# Arduino_extension_connectors.net
KiCad netlist of a schematic drawn in Altium Designer
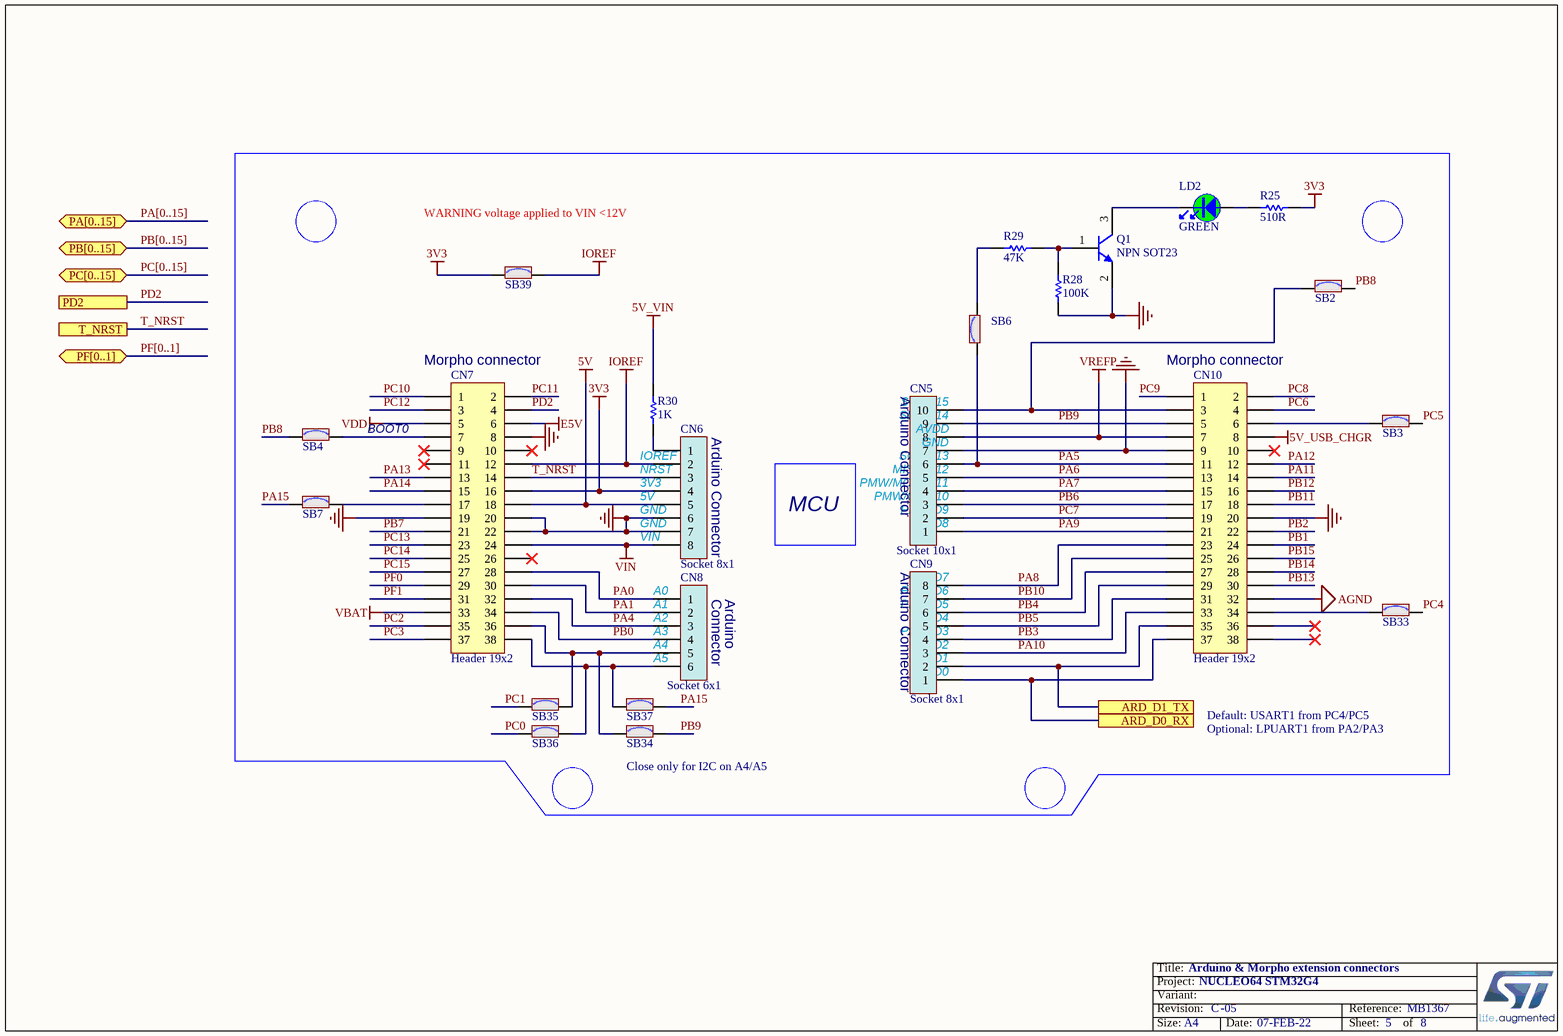
[diagram p0: Arduino_extension_connectors.SchDoc]

(export (version "E")
  (design (tool "Eeschema 10.0.6"))
  (components
    (comp (ref "CN5")
      (value "Socket 10x1")
      (footprint "CON_SAMTEC_SSW-110-03-X-S")
      (description "Socket, 10x1, 2.54mm, VR, TH, Height 8.51mm/10mm")
      (fields
        (field (name "INTERNAL_PART_NUMBER") "MCD-00262")
        (field (name "MANUFACTURER_PART_NUMBER") "SSW-110-03-x-S")
        (field (name "PROVIDED_BY") "SUBCO")
      )
      (libsource (lib "MCD_PARTS_database") (part "Socket 10x1"))
    )
    (comp (ref "CN6")
      (value "Socket 8x1")
      (footprint "CON_SAMTEC_SSW-108-03-X-S")
      (description "Socket, 8x1, 2.54mm, VR, TH, Height 8.51mm/10mm")
      (fields
        (field (name "INTERNAL_PART_NUMBER") "MCD-00261")
        (field (name "MANUFACTURER_PART_NUMBER") "SSW-108-03-x-S")
        (field (name "PROVIDED_BY") "SUBCO")
      )
      (libsource (lib "MCD_PARTS_database") (part "Socket 8x1"))
    )
    (comp (ref "CN7")
      (value "Header 19x2")
      (footprint "CON_SAMTEC_TSW-119-09-X-D")
      (description "Header, 19x2, 2,54mm, VR, TH, Height 5.84mm/10.16mm")
      (fields
        (field (name "INTERNAL_PART_NUMBER") "MCD-00213")
        (field (name "MANUFACTURER_PART_NUMBER") "TSW-119-09-x-D")
        (field (name "PROVIDED_BY") "SUBCO")
      )
      (libsource (lib "MCD_PARTS_database") (part "Header 19x2"))
    )
    (comp (ref "CN8")
      (value "Socket 6x1")
      (footprint "CON_SAMTEC_SSW-106-03-X-S")
      (description "Socket, 6x1, 2.54mm, VR, TH, Height 8.51mm/10mm")
      (fields
        (field (name "INTERNAL_PART_NUMBER") "MCD-00260")
        (field (name "MANUFACTURER_PART_NUMBER") "SSW-106-03-x-S")
        (field (name "PROVIDED_BY") "SUBCO")
      )
      (libsource (lib "MCD_PARTS_database") (part "Socket 6x1"))
    )
    (comp (ref "CN9")
      (value "Socket 8x1")
      (footprint "CON_SAMTEC_SSW-108-03-X-S")
      (description "Socket, 8x1, 2.54mm, VR, TH, Height 8.51mm/10mm")
      (fields
        (field (name "INTERNAL_PART_NUMBER") "MCD-00261")
        (field (name "MANUFACTURER_PART_NUMBER") "SSW-108-03-x-S")
        (field (name "PROVIDED_BY") "SUBCO")
      )
      (libsource (lib "") (part "Socket 8x1_1"))
    )
    (comp (ref "CN10")
      (value "Header 19x2")
      (footprint "CON_SAMTEC_TSW-119-09-X-D")
      (description "Header, 19x2, 2,54mm, VR, TH, Height 5.84mm/10.16mm")
      (fields
        (field (name "INTERNAL_PART_NUMBER") "MCD-00213")
        (field (name "MANUFACTURER_PART_NUMBER") "TSW-119-09-x-D")
        (field (name "PROVIDED_BY") "SUBCO")
      )
      (libsource (lib "MCD_PARTS_database") (part "Header 19x2"))
    )
    (comp (ref "LD2")
      (value "GREEN")
      (footprint "LED_0603_GREEN")
      (description "LED, GREEN, 0603, VF : 2.4V max ; IF: 20mA")
      (fields
        (field (name "INTERNAL_PART_NUMBER") "MCD-02520")
        (field (name "MANUFACTURER") "OSRAM OPTO SEMICONDUCTORS")
      )
      (libsource (lib "MCD_PARTS_database") (part "LED_green"))
    )
    (comp (ref "Q1")
      (value "NPN SOT23")
      (footprint "NPN_SOT23")
      (description "NPN Bipolar Transistor")
      (fields
        (field (name "INTERNAL_PART_NUMBER") "MCD-00073")
        (field (name "MANUFACTURER_PART_NUMBER") "BSR14")
        (field (name "PROVIDED_BY") "SUBCO")
      )
      (libsource (lib "MCD_PARTS_database") (part "9013-SOT23"))
    )
    (comp (ref "R25")
      (value "510R")
      (footprint "R0603")
      (description "Resistor,510R,0603,1%,1/10W")
      (fields
        (field (name "INTERNAL_PART_NUMBER") "MCD-00225")
        (field (name "MANUFACTURER_PART_NUMBER") "RC0603FR-07510RL")
        (field (name "PROVIDED_BY") "SUBCO")
      )
      (libsource (lib "MCD_PARTS_database") (part "Resistor"))
    )
    (comp (ref "R28")
      (value "100K")
      (footprint "R0603")
      (description "Resistor,100K,0603,1%,1/10W")
      (fields
        (field (name "INTERNAL_PART_NUMBER") "MCD-00223")
        (field (name "MANUFACTURER_PART_NUMBER") "RC0603FR-07100KL")
        (field (name "PROVIDED_BY") "Subcon")
      )
      (libsource (lib "MCD_PARTS_database") (part "Resistor"))
    )
    (comp (ref "R29")
      (value "47K")
      (footprint "R0603")
      (description "Resistor,47K,0603,1%,1/10W")
      (fields
        (field (name "INTERNAL_PART_NUMBER") "MCD-00222")
        (field (name "MANUFACTURER_PART_NUMBER") "RC0603FR-0747KL")
        (field (name "PROVIDED_BY") "SUBCO")
      )
      (libsource (lib "MCD_PARTS_database") (part "Resistor"))
    )
    (comp (ref "R30")
      (value "1K")
      (footprint "R0603")
      (description "Resistor,1K,0603,1%,1/10W")
      (fields
        (field (name "INTERNAL_PART_NUMBER") "MCD-00070")
        (field (name "MANUFACTURER_PART_NUMBER") "RC0603FR-071KL")
        (field (name "PROVIDED_BY") "Subcon")
      )
      (libsource (lib "MCD_PARTS_database") (part "Resistor"))
    )
    (comp (ref "SB2")
      (value "~")
      (footprint "SOLDER-BRIDGE_R0603-0R")
      (description "Solder Bridge ON")
      (fields
        (field (name "INTERNAL_PART_NUMBER") "MCD-00071")
        (field (name "MANUFACTURER_PART_NUMBER") "RC0603JR-070RL")
        (field (name "PROVIDED_BY") "SUBCO")
      )
      (libsource (lib "MCD_PARTS_database") (part "SB_ON"))
    )
    (comp (ref "SB3")
      (value "~")
      (footprint "SOLDER-BRIDGE_R0603-0R")
      (description "Solder Bridge ON")
      (fields
        (field (name "INTERNAL_PART_NUMBER") "MCD-00071")
        (field (name "MANUFACTURER_PART_NUMBER") "RC0603JR-070RL")
        (field (name "PROVIDED_BY") "SUBCO")
      )
      (libsource (lib "MCD_PARTS_database") (part "SB_ON"))
    )
    (comp (ref "SB4")
      (value "~")
      (footprint "SOLDER-BRIDGE_R0603-0R")
      (description "Solder Bridge ON")
      (fields
        (field (name "INTERNAL_PART_NUMBER") "MCD-00071")
        (field (name "MANUFACTURER_PART_NUMBER") "RC0603JR-070RL")
        (field (name "PROVIDED_BY") "SUBCO")
      )
      (libsource (lib "MCD_PARTS_database") (part "SB_ON"))
    )
    (comp (ref "SB6")
      (value "~")
      (footprint "SOLDER-BRIDGE_R0603-0R")
      (description "Solder Bridge ON")
      (fields
        (field (name "INTERNAL_PART_NUMBER") "MCD-00071")
        (field (name "MANUFACTURER_PART_NUMBER") "RC0603JR-070RL")
        (field (name "PROVIDED_BY") "SUBCO")
      )
      (libsource (lib "") (part "SB_ON_1"))
    )
    (comp (ref "SB7")
      (value "~")
      (footprint "SOLDER-BRIDGE_R0603-0R")
      (description "Solder Bridge ON")
      (fields
        (field (name "INTERNAL_PART_NUMBER") "MCD-00071")
        (field (name "MANUFACTURER_PART_NUMBER") "RC0603JR-070RL")
        (field (name "PROVIDED_BY") "SUBCO")
      )
      (libsource (lib "MCD_PARTS_database") (part "SB_ON"))
    )
    (comp (ref "SB33")
      (value "~")
      (footprint "SOLDER-BRIDGE_R0603-0R")
      (description "Solder Bridge ON")
      (fields
        (field (name "INTERNAL_PART_NUMBER") "MCD-00071")
        (field (name "MANUFACTURER_PART_NUMBER") "RC0603JR-070RL")
        (field (name "PROVIDED_BY") "SUBCO")
      )
      (libsource (lib "MCD_PARTS_database") (part "SB_ON"))
    )
    (comp (ref "SB34")
      (value "~")
      (footprint "SOLDER-BRIDGE_R0603-0R")
      (description "Solder Bridge ON")
      (fields
        (field (name "INTERNAL_PART_NUMBER") "MCD-00071")
        (field (name "MANUFACTURER_PART_NUMBER") "RC0603JR-070RL")
        (field (name "PROVIDED_BY") "SUBCO")
      )
      (libsource (lib "MCD_PARTS_database") (part "SB_ON"))
    )
    (comp (ref "SB35")
      (value "~")
      (footprint "SOLDER-BRIDGE_R0603-0R")
      (description "Solder Bridge ON")
      (fields
        (field (name "INTERNAL_PART_NUMBER") "MCD-00071")
        (field (name "MANUFACTURER_PART_NUMBER") "RC0603JR-070RL")
        (field (name "PROVIDED_BY") "SUBCO")
      )
      (libsource (lib "MCD_PARTS_database") (part "SB_ON"))
    )
    (comp (ref "SB36")
      (value "~")
      (footprint "SOLDER-BRIDGE_R0603-0R")
      (description "Solder Bridge ON")
      (fields
        (field (name "INTERNAL_PART_NUMBER") "MCD-00071")
        (field (name "MANUFACTURER_PART_NUMBER") "RC0603JR-070RL")
        (field (name "PROVIDED_BY") "SUBCO")
      )
      (libsource (lib "MCD_PARTS_database") (part "SB_ON"))
    )
    (comp (ref "SB37")
      (value "~")
      (footprint "SOLDER-BRIDGE_R0603-0R")
      (description "Solder Bridge ON")
      (fields
        (field (name "INTERNAL_PART_NUMBER") "MCD-00071")
        (field (name "MANUFACTURER_PART_NUMBER") "RC0603JR-070RL")
        (field (name "PROVIDED_BY") "SUBCO")
      )
      (libsource (lib "MCD_PARTS_database") (part "SB_ON"))
    )
    (comp (ref "SB39")
      (value "~")
      (footprint "SOLDER-BRIDGE_R0603-0R")
      (description "Solder Bridge ON")
      (fields
        (field (name "INTERNAL_PART_NUMBER") "MCD-00071")
        (field (name "MANUFACTURER_PART_NUMBER") "RC0603JR-070RL")
        (field (name "PROVIDED_BY") "SUBCO")
      )
      (libsource (lib "MCD_PARTS_database") (part "SB_ON"))
    )
  )
  (nets
    (net (code "3") (name "/ARD_D0_RX") (class "Default")
      (node (ref "CN10") (pin "37") (pinfunction "37_37") (pintype "passive"))
      (node (ref "CN9") (pin "1") (pinfunction "1_1") (pintype "passive"))
    )
    (net (code "4") (name "/ARD_D1_TX") (class "Default")
      (node (ref "CN10") (pin "35") (pinfunction "35_35") (pintype "passive"))
      (node (ref "CN9") (pin "2") (pinfunction "2_2") (pintype "passive"))
    )
    (net (code "5") (name "/PA0") (class "Default")
      (node (ref "CN7") (pin "28") (pinfunction "28_28") (pintype "passive"))
      (node (ref "CN8") (pin "1") (pinfunction "1_1") (pintype "passive"))
    )
    (net (code "6") (name "/PA1") (class "Default")
      (node (ref "CN7") (pin "30") (pinfunction "30_30") (pintype "passive"))
      (node (ref "CN8") (pin "2") (pinfunction "2_2") (pintype "passive"))
    )
    (net (code "7") (name "/PA4") (class "Default")
      (node (ref "CN7") (pin "32") (pinfunction "32_32") (pintype "passive"))
      (node (ref "CN8") (pin "3") (pinfunction "3_3") (pintype "passive"))
    )
    (net (code "8") (name "/PA5") (class "Default")
      (node (ref "CN10") (pin "11") (pinfunction "11_11") (pintype "passive"))
      (node (ref "CN5") (pin "6") (pinfunction "6_6") (pintype "passive"))
      (node (ref "SB6") (pin "1") (pinfunction "1_1") (pintype "passive"))
    )
    (net (code "9") (name "/PA6") (class "Default")
      (node (ref "CN10") (pin "13") (pinfunction "13_13") (pintype "passive"))
      (node (ref "CN5") (pin "5") (pinfunction "5_5") (pintype "passive"))
    )
    (net (code "10") (name "/PA7") (class "Default")
      (node (ref "CN10") (pin "15") (pinfunction "15_15") (pintype "passive"))
      (node (ref "CN5") (pin "4") (pinfunction "4_4") (pintype "passive"))
    )
    (net (code "11") (name "/PA8") (class "Default")
      (node (ref "CN10") (pin "23") (pinfunction "23_23") (pintype "passive"))
      (node (ref "CN9") (pin "8") (pinfunction "8_8") (pintype "passive"))
    )
    (net (code "12") (name "/PA9") (class "Default")
      (node (ref "CN10") (pin "21") (pinfunction "21_21") (pintype "passive"))
      (node (ref "CN5") (pin "1") (pinfunction "1_1") (pintype "passive"))
    )
    (net (code "13") (name "/PA10") (class "Default")
      (node (ref "CN10") (pin "33") (pinfunction "33_33") (pintype "passive"))
      (node (ref "CN9") (pin "3") (pinfunction "3_3") (pintype "passive"))
    )
    (net (code "14") (name "/PA11") (class "Default")
      (node (ref "CN10") (pin "14") (pinfunction "14_14") (pintype "passive"))
    )
    (net (code "15") (name "/PA12") (class "Default")
      (node (ref "CN10") (pin "12") (pinfunction "12_12") (pintype "passive"))
    )
    (net (code "16") (name "/PA13") (class "Default")
      (node (ref "CN7") (pin "13") (pinfunction "13_13") (pintype "passive"))
    )
    (net (code "17") (name "/PA14") (class "Default")
      (node (ref "CN7") (pin "15") (pinfunction "15_15") (pintype "passive"))
    )
    (net (code "18") (name "/PA15") (class "Default")
      (node (ref "SB37") (pin "2") (pinfunction "2_2") (pintype "passive"))
      (node (ref "SB7") (pin "1") (pinfunction "1_1") (pintype "passive"))
    )
    (net (code "20") (name "/PB0") (class "Default")
      (node (ref "CN7") (pin "34") (pinfunction "34_34") (pintype "passive"))
      (node (ref "CN8") (pin "4") (pinfunction "4_4") (pintype "passive"))
    )
    (net (code "21") (name "/PB1") (class "Default")
      (node (ref "CN10") (pin "24") (pinfunction "24_24") (pintype "passive"))
    )
    (net (code "22") (name "/PB2") (class "Default")
      (node (ref "CN10") (pin "22") (pinfunction "22_22") (pintype "passive"))
    )
    (net (code "23") (name "/PB3") (class "Default")
      (node (ref "CN10") (pin "31") (pinfunction "31_31") (pintype "passive"))
      (node (ref "CN9") (pin "4") (pinfunction "4_4") (pintype "passive"))
    )
    (net (code "24") (name "/PB4") (class "Default")
      (node (ref "CN10") (pin "27") (pinfunction "27_27") (pintype "passive"))
      (node (ref "CN9") (pin "6") (pinfunction "6_6") (pintype "passive"))
    )
    (net (code "25") (name "/PB5") (class "Default")
      (node (ref "CN10") (pin "29") (pinfunction "29_29") (pintype "passive"))
      (node (ref "CN9") (pin "5") (pinfunction "5_5") (pintype "passive"))
    )
    (net (code "26") (name "/PB6") (class "Default")
      (node (ref "CN10") (pin "17") (pinfunction "17_17") (pintype "passive"))
      (node (ref "CN5") (pin "3") (pinfunction "3_3") (pintype "passive"))
    )
    (net (code "27") (name "/PB7") (class "Default")
      (node (ref "CN7") (pin "21") (pinfunction "21_21") (pintype "passive"))
    )
    (net (code "28") (name "/PB8") (class "Default")
      (node (ref "SB2") (pin "2") (pinfunction "2_2") (pintype "passive"))
      (node (ref "SB4") (pin "1") (pinfunction "1_1") (pintype "passive"))
    )
    (net (code "29") (name "/PB9") (class "Default")
      (node (ref "CN10") (pin "5") (pinfunction "5_5") (pintype "passive"))
      (node (ref "CN5") (pin "9") (pinfunction "9_9") (pintype "passive"))
      (node (ref "SB34") (pin "2") (pinfunction "2_2") (pintype "passive"))
    )
    (net (code "30") (name "/PB10") (class "Default")
      (node (ref "CN10") (pin "25") (pinfunction "25_25") (pintype "passive"))
      (node (ref "CN9") (pin "7") (pinfunction "7_7") (pintype "passive"))
    )
    (net (code "31") (name "/PB11") (class "Default")
      (node (ref "CN10") (pin "18") (pinfunction "18_18") (pintype "passive"))
    )
    (net (code "32") (name "/PB12") (class "Default")
      (node (ref "CN10") (pin "16") (pinfunction "16_16") (pintype "passive"))
    )
    (net (code "33") (name "/PB13") (class "Default")
      (node (ref "CN10") (pin "30") (pinfunction "30_30") (pintype "passive"))
    )
    (net (code "34") (name "/PB14") (class "Default")
      (node (ref "CN10") (pin "28") (pinfunction "28_28") (pintype "passive"))
    )
    (net (code "35") (name "/PB15") (class "Default")
      (node (ref "CN10") (pin "26") (pinfunction "26_26") (pintype "passive"))
    )
    (net (code "37") (name "/PC0") (class "Default")
      (node (ref "SB36") (pin "1") (pinfunction "1_1") (pintype "passive"))
    )
    (net (code "38") (name "/PC1") (class "Default")
      (node (ref "SB35") (pin "1") (pinfunction "1_1") (pintype "passive"))
    )
    (net (code "39") (name "/PC2") (class "Default")
      (node (ref "CN7") (pin "35") (pinfunction "35_35") (pintype "passive"))
    )
    (net (code "40") (name "/PC3") (class "Default")
      (node (ref "CN7") (pin "37") (pinfunction "37_37") (pintype "passive"))
    )
    (net (code "41") (name "/PC4") (class "Default")
      (node (ref "SB33") (pin "2") (pinfunction "2_2") (pintype "passive"))
    )
    (net (code "42") (name "/PC5") (class "Default")
      (node (ref "SB3") (pin "2") (pinfunction "2_2") (pintype "passive"))
    )
    (net (code "43") (name "/PC6") (class "Default")
      (node (ref "CN10") (pin "4") (pinfunction "4_4") (pintype "passive"))
    )
    (net (code "44") (name "/PC7") (class "Default")
      (node (ref "CN10") (pin "19") (pinfunction "19_19") (pintype "passive"))
      (node (ref "CN5") (pin "2") (pinfunction "2_2") (pintype "passive"))
    )
    (net (code "45") (name "/PC8") (class "Default")
      (node (ref "CN10") (pin "2") (pinfunction "2_2") (pintype "passive"))
    )
    (net (code "46") (name "/PC9") (class "Default")
      (node (ref "CN10") (pin "1") (pinfunction "1_1") (pintype "passive"))
    )
    (net (code "47") (name "/PC10") (class "Default")
      (node (ref "CN7") (pin "1") (pinfunction "1_1") (pintype "passive"))
    )
    (net (code "48") (name "/PC11") (class "Default")
      (node (ref "CN7") (pin "2") (pinfunction "2_2") (pintype "passive"))
    )
    (net (code "49") (name "/PC12") (class "Default")
      (node (ref "CN7") (pin "3") (pinfunction "3_3") (pintype "passive"))
    )
    (net (code "50") (name "/PC13") (class "Default")
      (node (ref "CN7") (pin "23") (pinfunction "23_23") (pintype "passive"))
    )
    (net (code "51") (name "/PC14") (class "Default")
      (node (ref "CN7") (pin "25") (pinfunction "25_25") (pintype "passive"))
    )
    (net (code "52") (name "/PC15") (class "Default")
      (node (ref "CN7") (pin "27") (pinfunction "27_27") (pintype "passive"))
    )
    (net (code "54") (name "/PD2") (class "Default")
      (node (ref "CN7") (pin "4") (pinfunction "4_4") (pintype "passive"))
    )
    (net (code "55") (name "/PF0") (class "Default")
      (node (ref "CN7") (pin "29") (pinfunction "29_29") (pintype "passive"))
    )
    (net (code "56") (name "/PF1") (class "Default")
      (node (ref "CN7") (pin "31") (pinfunction "31_31") (pintype "passive"))
    )
    (net (code "58") (name "/T_NRST") (class "Default")
      (node (ref "CN6") (pin "3") (pinfunction "3_3") (pintype "passive"))
      (node (ref "CN7") (pin "14") (pinfunction "14_14") (pintype "passive"))
    )
    (net (code "59") (name "3V3") (class "Default")
      (node (ref "CN6") (pin "4") (pinfunction "4_4") (pintype "passive"))
      (node (ref "CN7") (pin "16") (pinfunction "16_16") (pintype "passive"))
      (node (ref "R25") (pin "1") (pinfunction "1_1") (pintype "passive"))
      (node (ref "SB39") (pin "1") (pinfunction "1_1") (pintype "passive"))
    )
    (net (code "60") (name "5V") (class "Default")
      (node (ref "CN6") (pin "5") (pinfunction "5_5") (pintype "passive"))
      (node (ref "CN7") (pin "18") (pinfunction "18_18") (pintype "passive"))
    )
    (net (code "61") (name "5V_USB_CHGR") (class "Default")
      (node (ref "CN10") (pin "8") (pinfunction "8_8") (pintype "passive"))
    )
    (net (code "62") (name "5V_VIN") (class "Default")
      (node (ref "R30") (pin "2") (pinfunction "2_2") (pintype "passive"))
    )
    (net (code "63") (name "AGND") (class "Default")
      (node (ref "CN10") (pin "32") (pinfunction "32_32") (pintype "passive"))
    )
    (net (code "64") (name "E5V") (class "Default")
      (node (ref "CN7") (pin "6") (pinfunction "6_6") (pintype "passive"))
    )
    (net (code "65") (name "GND") (class "Default")
      (node (ref "CN10") (pin "20") (pinfunction "20_20") (pintype "passive"))
      (node (ref "CN10") (pin "9") (pinfunction "9_9") (pintype "passive"))
      (node (ref "CN5") (pin "7") (pinfunction "7_7") (pintype "passive"))
      (node (ref "CN6") (pin "6") (pinfunction "6_6") (pintype "passive"))
      (node (ref "CN6") (pin "7") (pinfunction "7_7") (pintype "passive"))
      (node (ref "CN7") (pin "19") (pinfunction "19_19") (pintype "passive"))
      (node (ref "CN7") (pin "20") (pinfunction "20_20") (pintype "passive"))
      (node (ref "CN7") (pin "22") (pinfunction "22_22") (pintype "passive"))
      (node (ref "CN7") (pin "8") (pinfunction "8_8") (pintype "passive"))
      (node (ref "Q1") (pin "2") (pinfunction "E_2") (pintype "passive"))
      (node (ref "R28") (pin "1") (pinfunction "1_1") (pintype "passive"))
    )
    (net (code "66") (name "IOREF") (class "Default")
      (node (ref "CN6") (pin "2") (pinfunction "2_2") (pintype "passive"))
      (node (ref "CN7") (pin "12") (pinfunction "12_12") (pintype "passive"))
      (node (ref "SB39") (pin "2") (pinfunction "2_2") (pintype "passive"))
    )
    (net (code "67") (name "Net-(CN6-Pad1)") (class "Default")
      (node (ref "CN6") (pin "1") (pinfunction "1_1") (pintype "passive"))
      (node (ref "R30") (pin "1") (pinfunction "1_1") (pintype "passive"))
    )
    (net (code "68") (name "Net-(CN7-Pad7)") (class "Default")
      (node (ref "CN7") (pin "7") (pinfunction "7_7") (pintype "passive"))
      (node (ref "SB4") (pin "2") (pinfunction "2_2") (pintype "passive"))
    )
    (net (code "69") (name "Net-(CN7-Pad17)") (class "Default")
      (node (ref "CN7") (pin "17") (pinfunction "17_17") (pintype "passive"))
      (node (ref "SB7") (pin "2") (pinfunction "2_2") (pintype "passive"))
    )
    (net (code "70") (name "Net-(CN7-Pad36)") (class "Default")
      (node (ref "CN7") (pin "36") (pinfunction "36_36") (pintype "passive"))
      (node (ref "CN8") (pin "5") (pinfunction "5_5") (pintype "passive"))
      (node (ref "SB34") (pin "1") (pinfunction "1_1") (pintype "passive"))
      (node (ref "SB35") (pin "2") (pinfunction "2_2") (pintype "passive"))
    )
    (net (code "71") (name "Net-(CN7-Pad38)") (class "Default")
      (node (ref "CN7") (pin "38") (pinfunction "38_38") (pintype "passive"))
      (node (ref "CN8") (pin "6") (pinfunction "6_6") (pintype "passive"))
      (node (ref "SB36") (pin "2") (pinfunction "2_2") (pintype "passive"))
      (node (ref "SB37") (pin "1") (pinfunction "1_1") (pintype "passive"))
    )
    (net (code "72") (name "Net-(CN10-Pad3)") (class "Default")
      (node (ref "CN10") (pin "3") (pinfunction "3_3") (pintype "passive"))
      (node (ref "CN5") (pin "10") (pinfunction "10_10") (pintype "passive"))
      (node (ref "SB2") (pin "1") (pinfunction "1_1") (pintype "passive"))
    )
    (net (code "73") (name "Net-(CN10-Pad6)") (class "Default")
      (node (ref "CN10") (pin "6") (pinfunction "6_6") (pintype "passive"))
      (node (ref "SB3") (pin "1") (pinfunction "1_1") (pintype "passive"))
    )
    (net (code "74") (name "Net-(CN10-Pad34)") (class "Default")
      (node (ref "CN10") (pin "34") (pinfunction "34_34") (pintype "passive"))
      (node (ref "SB33") (pin "1") (pinfunction "1_1") (pintype "passive"))
    )
    (net (code "75") (name "Net-(LD2-Pad1)") (class "Default")
      (node (ref "LD2") (pin "1") (pintype "passive"))
      (node (ref "R25") (pin "2") (pinfunction "2_2") (pintype "passive"))
    )
    (net (code "76") (name "Net-(Q1-B)") (class "Default")
      (node (ref "Q1") (pin "1") (pinfunction "B_1") (pintype "passive"))
      (node (ref "R28") (pin "2") (pinfunction "2_2") (pintype "passive"))
      (node (ref "R29") (pin "2") (pinfunction "2_2") (pintype "passive"))
    )
    (net (code "77") (name "Net-(Q1-C)") (class "Default")
      (node (ref "LD2") (pin "2") (pintype "passive"))
      (node (ref "Q1") (pin "3") (pinfunction "C_3") (pintype "passive"))
    )
    (net (code "78") (name "Net-(R29-Pad1)") (class "Default")
      (node (ref "R29") (pin "1") (pinfunction "1_1") (pintype "passive"))
      (node (ref "SB6") (pin "2") (pinfunction "2_2") (pintype "passive"))
    )
    (net (code "79") (name "VBAT") (class "Default")
      (node (ref "CN7") (pin "33") (pinfunction "33_33") (pintype "passive"))
    )
    (net (code "80") (name "VDD") (class "Default")
      (node (ref "CN7") (pin "5") (pinfunction "5_5") (pintype "passive"))
    )
    (net (code "81") (name "VIN") (class "Default")
      (node (ref "CN6") (pin "8") (pinfunction "8_8") (pintype "passive"))
      (node (ref "CN7") (pin "24") (pinfunction "24_24") (pintype "passive"))
    )
    (net (code "82") (name "VREFP") (class "Default")
      (node (ref "CN10") (pin "7") (pinfunction "7_7") (pintype "passive"))
      (node (ref "CN5") (pin "8") (pinfunction "8_8") (pintype "passive"))
    )
    (net (code "83") (name "unconnected-(CN7-Pad9)") (class "Default")
      (node (ref "CN7") (pin "9") (pinfunction "9_9") (pintype "passive+no_connect"))
    )
    (net (code "84") (name "unconnected-(CN7-Pad10)") (class "Default")
      (node (ref "CN7") (pin "10") (pinfunction "10_10") (pintype "passive+no_connect"))
    )
    (net (code "85") (name "unconnected-(CN7-Pad11)") (class "Default")
      (node (ref "CN7") (pin "11") (pinfunction "11_11") (pintype "passive+no_connect"))
    )
    (net (code "86") (name "unconnected-(CN7-Pad26)") (class "Default")
      (node (ref "CN7") (pin "26") (pinfunction "26_26") (pintype "passive+no_connect"))
    )
    (net (code "87") (name "unconnected-(CN10-Pad10)") (class "Default")
      (node (ref "CN10") (pin "10") (pinfunction "10_10") (pintype "passive+no_connect"))
    )
    (net (code "88") (name "unconnected-(CN10-Pad36)") (class "Default")
      (node (ref "CN10") (pin "36") (pinfunction "36_36") (pintype "passive+no_connect"))
    )
    (net (code "89") (name "unconnected-(CN10-Pad38)") (class "Default")
      (node (ref "CN10") (pin "38") (pinfunction "38_38") (pintype "passive+no_connect"))
    )
  )
)
